# WiiIr.net
KiCad netlist of a schematic drawn in EAGLE
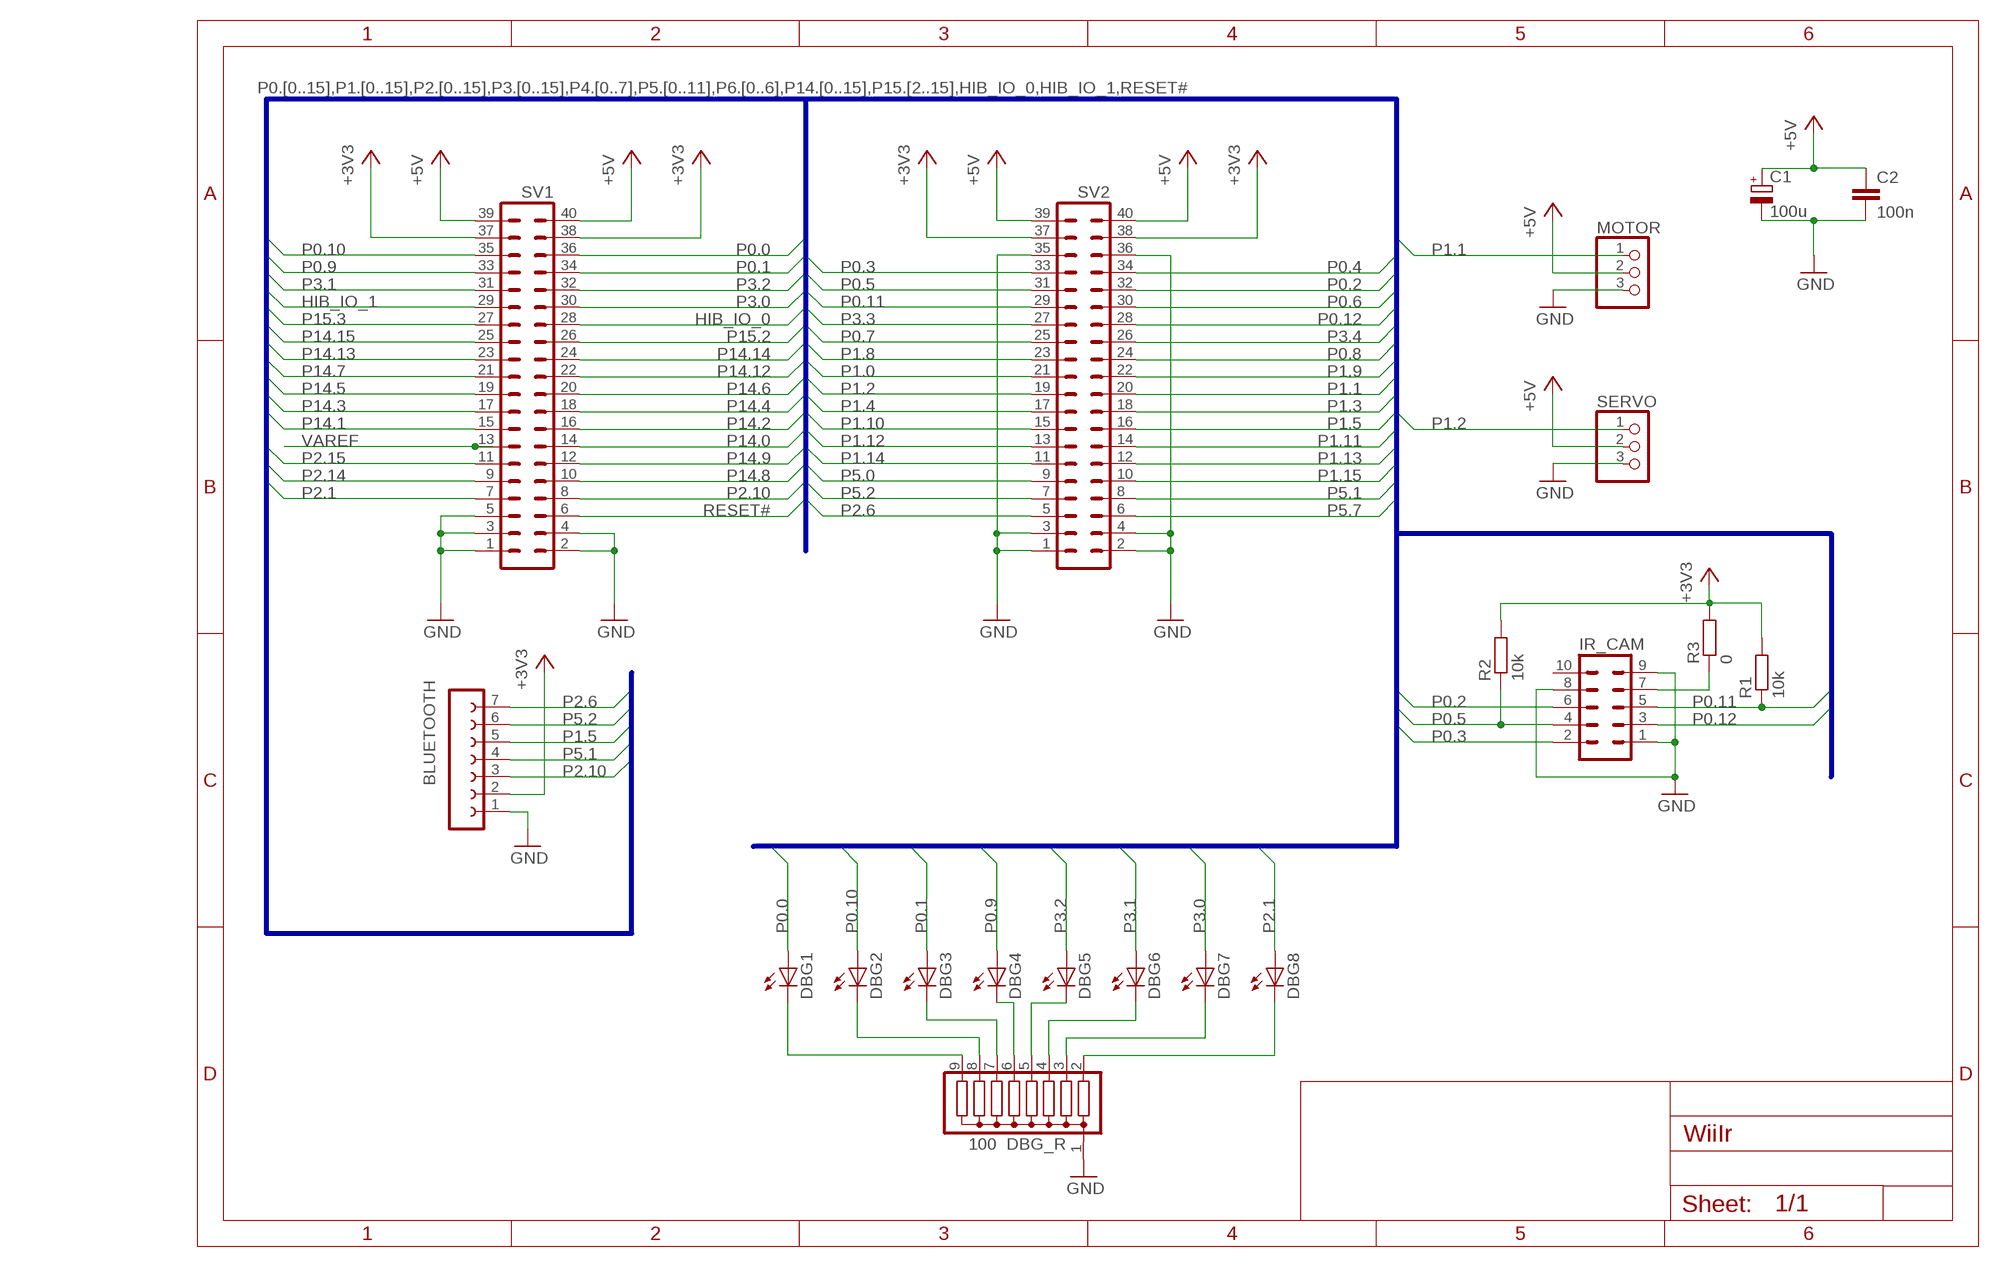
[diagram p0: schematic, sheet 1]

(export (version "E")
  (design (tool "Eeschema 10.0.6"))
  (components
    (comp (ref "BLUETOOTH")
      (value "FE07-1")
      (footprint "eagle-import:FE07")
      (libsource (lib "eagle-import") (part "FE07-1"))
    )
    (comp (ref "C1")
      (value "100u")
      (footprint "eagle-import:E2,5-7")
      (libsource (lib "eagle-import") (part "CPOL-EUE2.5-7"))
    )
    (comp (ref "C2")
      (value "100n")
      (footprint "eagle-import:C050-024X044")
      (libsource (lib "eagle-import") (part "C-EU050-024X044"))
    )
    (comp (ref "DBG1")
      (value "LEDSQR2X5")
      (footprint "eagle-import:LED2X5")
      (libsource (lib "eagle-import") (part "LEDSQR2X5"))
    )
    (comp (ref "DBG2")
      (value "LEDSQR2X5")
      (footprint "eagle-import:LED2X5")
      (libsource (lib "eagle-import") (part "LEDSQR2X5"))
    )
    (comp (ref "DBG3")
      (value "LEDSQR2X5")
      (footprint "eagle-import:LED2X5")
      (libsource (lib "eagle-import") (part "LEDSQR2X5"))
    )
    (comp (ref "DBG4")
      (value "LEDSQR2X5")
      (footprint "eagle-import:LED2X5")
      (libsource (lib "eagle-import") (part "LEDSQR2X5"))
    )
    (comp (ref "DBG5")
      (value "LEDSQR2X5")
      (footprint "eagle-import:LED2X5")
      (libsource (lib "eagle-import") (part "LEDSQR2X5"))
    )
    (comp (ref "DBG6")
      (value "LEDSQR2X5")
      (footprint "eagle-import:LED2X5")
      (libsource (lib "eagle-import") (part "LEDSQR2X5"))
    )
    (comp (ref "DBG7")
      (value "LEDSQR2X5")
      (footprint "eagle-import:LED2X5")
      (libsource (lib "eagle-import") (part "LEDSQR2X5"))
    )
    (comp (ref "DBG8")
      (value "LEDSQR2X5")
      (footprint "eagle-import:LED2X5")
      (libsource (lib "eagle-import") (part "LEDSQR2X5"))
    )
    (comp (ref "DBG_R")
      (value "100")
      (footprint "eagle-import:SIL9")
      (libsource (lib "eagle-import") (part "G08R"))
    )
    (comp (ref "IR_CAM")
      (value "ML10")
      (footprint "eagle-import:ML10")
      (libsource (lib "eagle-import") (part "ML10"))
    )
    (comp (ref "MOTOR")
      (value "PINHD-1X3/90")
      (footprint "eagle-import:1X03_90")
      (libsource (lib "eagle-import") (part "PINHD-1X3/90"))
    )
    (comp (ref "R1")
      (value "10k")
      (footprint "eagle-import:0207_10")
      (libsource (lib "eagle-import") (part "R-EU_0207/10"))
    )
    (comp (ref "R2")
      (value "10k")
      (footprint "eagle-import:0207_10")
      (libsource (lib "eagle-import") (part "R-EU_0207/10"))
    )
    (comp (ref "R3")
      (value "0")
      (footprint "eagle-import:0207_12")
      (libsource (lib "eagle-import") (part "R-EU_0207/12"))
    )
    (comp (ref "SERVO")
      (value "PINHD-1X3/90")
      (footprint "eagle-import:1X03_90")
      (libsource (lib "eagle-import") (part "PINHD-1X3/90"))
    )
    (comp (ref "SV1")
      (value "MA20-2")
      (footprint "eagle-import:MA20-2")
      (libsource (lib "eagle-import") (part "MA20-2"))
    )
    (comp (ref "SV2")
      (value "MA20-2")
      (footprint "eagle-import:MA20-2")
      (libsource (lib "eagle-import") (part "MA20-2"))
    )
  )
  (nets
    (net (code "1") (name "+3V3") (class "Default")
      (node (ref "BLUETOOTH") (pin "2") (pinfunction "2_2") (pintype "passive"))
      (node (ref "R1") (pin "2") (pinfunction "2_2") (pintype "passive"))
      (node (ref "R2") (pin "2") (pinfunction "2_2") (pintype "passive"))
      (node (ref "R3") (pin "2") (pinfunction "2_2") (pintype "passive"))
      (node (ref "SV1") (pin "37") (pinfunction "37_37") (pintype "passive"))
      (node (ref "SV1") (pin "38") (pinfunction "38_38") (pintype "passive"))
      (node (ref "SV2") (pin "37") (pinfunction "37_37") (pintype "passive"))
      (node (ref "SV2") (pin "38") (pinfunction "38_38") (pintype "passive"))
    )
    (net (code "2") (name "+5V") (class "Default")
      (node (ref "C1") (pin "+") (pinfunction "+_+") (pintype "passive"))
      (node (ref "C2") (pin "1") (pinfunction "1_1") (pintype "passive"))
      (node (ref "MOTOR") (pin "2") (pinfunction "2_2") (pintype "passive"))
      (node (ref "SERVO") (pin "2") (pinfunction "2_2") (pintype "passive"))
      (node (ref "SV1") (pin "39") (pinfunction "39_39") (pintype "passive"))
      (node (ref "SV1") (pin "40") (pinfunction "40_40") (pintype "passive"))
      (node (ref "SV2") (pin "39") (pinfunction "39_39") (pintype "passive"))
      (node (ref "SV2") (pin "40") (pinfunction "40_40") (pintype "passive"))
    )
    (net (code "3") (name "/HIB_IO_0") (class "Default")
      (node (ref "SV1") (pin "28") (pinfunction "28_28") (pintype "passive"))
    )
    (net (code "4") (name "/HIB_IO_1") (class "Default")
      (node (ref "SV1") (pin "29") (pinfunction "29_29") (pintype "passive"))
    )
    (net (code "5") (name "/P0.0") (class "Default")
      (node (ref "DBG1") (pin "A") (pinfunction "A_A") (pintype "passive"))
      (node (ref "SV1") (pin "36") (pinfunction "36_36") (pintype "passive"))
    )
    (net (code "6") (name "/P0.1") (class "Default")
      (node (ref "DBG3") (pin "A") (pinfunction "A_A") (pintype "passive"))
      (node (ref "SV1") (pin "34") (pinfunction "34_34") (pintype "passive"))
    )
    (net (code "7") (name "/P0.2") (class "Default")
      (node (ref "IR_CAM") (pin "6") (pinfunction "6_6") (pintype "passive"))
      (node (ref "SV2") (pin "32") (pinfunction "32_32") (pintype "passive"))
    )
    (net (code "8") (name "/P0.3") (class "Default")
      (node (ref "IR_CAM") (pin "2") (pinfunction "2_2") (pintype "passive"))
      (node (ref "SV2") (pin "33") (pinfunction "33_33") (pintype "passive"))
    )
    (net (code "9") (name "/P0.4") (class "Default")
      (node (ref "SV2") (pin "34") (pinfunction "34_34") (pintype "passive"))
    )
    (net (code "10") (name "/P0.5") (class "Default")
      (node (ref "IR_CAM") (pin "4") (pinfunction "4_4") (pintype "passive"))
      (node (ref "R2") (pin "1") (pinfunction "1_1") (pintype "passive"))
      (node (ref "SV2") (pin "31") (pinfunction "31_31") (pintype "passive"))
    )
    (net (code "11") (name "/P0.6") (class "Default")
      (node (ref "SV2") (pin "30") (pinfunction "30_30") (pintype "passive"))
    )
    (net (code "12") (name "/P0.7") (class "Default")
      (node (ref "SV2") (pin "25") (pinfunction "25_25") (pintype "passive"))
    )
    (net (code "13") (name "/P0.8") (class "Default")
      (node (ref "SV2") (pin "24") (pinfunction "24_24") (pintype "passive"))
    )
    (net (code "14") (name "/P0.9") (class "Default")
      (node (ref "DBG4") (pin "A") (pinfunction "A_A") (pintype "passive"))
      (node (ref "SV1") (pin "33") (pinfunction "33_33") (pintype "passive"))
    )
    (net (code "15") (name "/P0.10") (class "Default")
      (node (ref "DBG2") (pin "A") (pinfunction "A_A") (pintype "passive"))
      (node (ref "SV1") (pin "35") (pinfunction "35_35") (pintype "passive"))
    )
    (net (code "16") (name "/P0.11") (class "Default")
      (node (ref "IR_CAM") (pin "5") (pinfunction "5_5") (pintype "passive"))
      (node (ref "R1") (pin "1") (pinfunction "1_1") (pintype "passive"))
      (node (ref "SV2") (pin "29") (pinfunction "29_29") (pintype "passive"))
    )
    (net (code "17") (name "/P0.12") (class "Default")
      (node (ref "IR_CAM") (pin "3") (pinfunction "3_3") (pintype "passive"))
      (node (ref "SV2") (pin "28") (pinfunction "28_28") (pintype "passive"))
    )
    (net (code "18") (name "/P1.0") (class "Default")
      (node (ref "SV2") (pin "21") (pinfunction "21_21") (pintype "passive"))
    )
    (net (code "19") (name "/P1.1") (class "Default")
      (node (ref "MOTOR") (pin "1") (pinfunction "1_1") (pintype "passive"))
      (node (ref "SV2") (pin "20") (pinfunction "20_20") (pintype "passive"))
    )
    (net (code "20") (name "/P1.2") (class "Default")
      (node (ref "SERVO") (pin "1") (pinfunction "1_1") (pintype "passive"))
      (node (ref "SV2") (pin "19") (pinfunction "19_19") (pintype "passive"))
    )
    (net (code "21") (name "/P1.3") (class "Default")
      (node (ref "SV2") (pin "18") (pinfunction "18_18") (pintype "passive"))
    )
    (net (code "22") (name "/P1.4") (class "Default")
      (node (ref "SV2") (pin "17") (pinfunction "17_17") (pintype "passive"))
    )
    (net (code "23") (name "/P1.5") (class "Default")
      (node (ref "BLUETOOTH") (pin "5") (pinfunction "5_5") (pintype "passive"))
      (node (ref "SV2") (pin "16") (pinfunction "16_16") (pintype "passive"))
    )
    (net (code "24") (name "/P1.8") (class "Default")
      (node (ref "SV2") (pin "23") (pinfunction "23_23") (pintype "passive"))
    )
    (net (code "25") (name "/P1.9") (class "Default")
      (node (ref "SV2") (pin "22") (pinfunction "22_22") (pintype "passive"))
    )
    (net (code "26") (name "/P1.10") (class "Default")
      (node (ref "SV2") (pin "15") (pinfunction "15_15") (pintype "passive"))
    )
    (net (code "27") (name "/P1.11") (class "Default")
      (node (ref "SV2") (pin "14") (pinfunction "14_14") (pintype "passive"))
    )
    (net (code "28") (name "/P1.12") (class "Default")
      (node (ref "SV2") (pin "13") (pinfunction "13_13") (pintype "passive"))
    )
    (net (code "29") (name "/P1.13") (class "Default")
      (node (ref "SV2") (pin "12") (pinfunction "12_12") (pintype "passive"))
    )
    (net (code "30") (name "/P1.14") (class "Default")
      (node (ref "SV2") (pin "11") (pinfunction "11_11") (pintype "passive"))
    )
    (net (code "31") (name "/P1.15") (class "Default")
      (node (ref "SV2") (pin "10") (pinfunction "10_10") (pintype "passive"))
    )
    (net (code "32") (name "/P2.1") (class "Default")
      (node (ref "DBG8") (pin "A") (pinfunction "A_A") (pintype "passive"))
      (node (ref "SV1") (pin "7") (pinfunction "7_7") (pintype "passive"))
    )
    (net (code "33") (name "/P2.6") (class "Default")
      (node (ref "BLUETOOTH") (pin "7") (pinfunction "7_7") (pintype "passive"))
      (node (ref "SV2") (pin "5") (pinfunction "5_5") (pintype "passive"))
    )
    (net (code "34") (name "/P2.10") (class "Default")
      (node (ref "BLUETOOTH") (pin "3") (pinfunction "3_3") (pintype "passive"))
      (node (ref "SV1") (pin "8") (pinfunction "8_8") (pintype "passive"))
    )
    (net (code "35") (name "/P2.14") (class "Default")
      (node (ref "SV1") (pin "9") (pinfunction "9_9") (pintype "passive"))
    )
    (net (code "36") (name "/P2.15") (class "Default")
      (node (ref "SV1") (pin "11") (pinfunction "11_11") (pintype "passive"))
    )
    (net (code "37") (name "/P3.0") (class "Default")
      (node (ref "DBG7") (pin "A") (pinfunction "A_A") (pintype "passive"))
      (node (ref "SV1") (pin "30") (pinfunction "30_30") (pintype "passive"))
    )
    (net (code "38") (name "/P3.1") (class "Default")
      (node (ref "DBG6") (pin "A") (pinfunction "A_A") (pintype "passive"))
      (node (ref "SV1") (pin "31") (pinfunction "31_31") (pintype "passive"))
    )
    (net (code "39") (name "/P3.2") (class "Default")
      (node (ref "DBG5") (pin "A") (pinfunction "A_A") (pintype "passive"))
      (node (ref "SV1") (pin "32") (pinfunction "32_32") (pintype "passive"))
    )
    (net (code "40") (name "/P3.3") (class "Default")
      (node (ref "SV2") (pin "27") (pinfunction "27_27") (pintype "passive"))
    )
    (net (code "41") (name "/P3.4") (class "Default")
      (node (ref "SV2") (pin "26") (pinfunction "26_26") (pintype "passive"))
    )
    (net (code "42") (name "/P5.0") (class "Default")
      (node (ref "SV2") (pin "9") (pinfunction "9_9") (pintype "passive"))
    )
    (net (code "43") (name "/P5.1") (class "Default")
      (node (ref "BLUETOOTH") (pin "4") (pinfunction "4_4") (pintype "passive"))
      (node (ref "SV2") (pin "8") (pinfunction "8_8") (pintype "passive"))
    )
    (net (code "44") (name "/P5.2") (class "Default")
      (node (ref "BLUETOOTH") (pin "6") (pinfunction "6_6") (pintype "passive"))
      (node (ref "SV2") (pin "7") (pinfunction "7_7") (pintype "passive"))
    )
    (net (code "45") (name "/P5.7") (class "Default")
      (node (ref "SV2") (pin "6") (pinfunction "6_6") (pintype "passive"))
    )
    (net (code "46") (name "/P14.0") (class "Default")
      (node (ref "SV1") (pin "14") (pinfunction "14_14") (pintype "passive"))
    )
    (net (code "47") (name "/P14.1") (class "Default")
      (node (ref "SV1") (pin "15") (pinfunction "15_15") (pintype "passive"))
    )
    (net (code "48") (name "/P14.2") (class "Default")
      (node (ref "SV1") (pin "16") (pinfunction "16_16") (pintype "passive"))
    )
    (net (code "49") (name "/P14.3") (class "Default")
      (node (ref "SV1") (pin "17") (pinfunction "17_17") (pintype "passive"))
    )
    (net (code "50") (name "/P14.4") (class "Default")
      (node (ref "SV1") (pin "18") (pinfunction "18_18") (pintype "passive"))
    )
    (net (code "51") (name "/P14.5") (class "Default")
      (node (ref "SV1") (pin "19") (pinfunction "19_19") (pintype "passive"))
    )
    (net (code "52") (name "/P14.6") (class "Default")
      (node (ref "SV1") (pin "20") (pinfunction "20_20") (pintype "passive"))
    )
    (net (code "53") (name "/P14.7") (class "Default")
      (node (ref "SV1") (pin "21") (pinfunction "21_21") (pintype "passive"))
    )
    (net (code "54") (name "/P14.8") (class "Default")
      (node (ref "SV1") (pin "10") (pinfunction "10_10") (pintype "passive"))
    )
    (net (code "55") (name "/P14.9") (class "Default")
      (node (ref "SV1") (pin "12") (pinfunction "12_12") (pintype "passive"))
    )
    (net (code "56") (name "/P14.12") (class "Default")
      (node (ref "SV1") (pin "22") (pinfunction "22_22") (pintype "passive"))
    )
    (net (code "57") (name "/P14.13") (class "Default")
      (node (ref "SV1") (pin "23") (pinfunction "23_23") (pintype "passive"))
    )
    (net (code "58") (name "/P14.14") (class "Default")
      (node (ref "SV1") (pin "24") (pinfunction "24_24") (pintype "passive"))
    )
    (net (code "59") (name "/P14.15") (class "Default")
      (node (ref "SV1") (pin "25") (pinfunction "25_25") (pintype "passive"))
    )
    (net (code "60") (name "/P15.2") (class "Default")
      (node (ref "SV1") (pin "26") (pinfunction "26_26") (pintype "passive"))
    )
    (net (code "61") (name "/P15.3") (class "Default")
      (node (ref "SV1") (pin "27") (pinfunction "27_27") (pintype "passive"))
    )
    (net (code "62") (name "/RESET#") (class "Default")
      (node (ref "SV1") (pin "6") (pinfunction "6_6") (pintype "passive"))
    )
    (net (code "63") (name "/VAREF") (class "Default")
      (node (ref "SV1") (pin "13") (pinfunction "13_13") (pintype "passive"))
    )
    (net (code "65") (name "GND") (class "Default")
      (node (ref "BLUETOOTH") (pin "1") (pinfunction "1_1") (pintype "passive"))
      (node (ref "C1") (pin "-") (pinfunction "-_-") (pintype "passive"))
      (node (ref "C2") (pin "2") (pinfunction "2_2") (pintype "passive"))
      (node (ref "DBG_R") (pin "1") (pinfunction "1_1") (pintype "passive"))
      (node (ref "IR_CAM") (pin "1") (pinfunction "1_1") (pintype "passive"))
      (node (ref "IR_CAM") (pin "8") (pinfunction "8_8") (pintype "passive"))
      (node (ref "IR_CAM") (pin "9") (pinfunction "9_9") (pintype "passive"))
      (node (ref "MOTOR") (pin "3") (pinfunction "3_3") (pintype "passive"))
      (node (ref "SERVO") (pin "3") (pinfunction "3_3") (pintype "passive"))
      (node (ref "SV1") (pin "1") (pinfunction "1_1") (pintype "passive"))
      (node (ref "SV1") (pin "2") (pinfunction "2_2") (pintype "passive"))
      (node (ref "SV1") (pin "3") (pinfunction "3_3") (pintype "passive"))
      (node (ref "SV1") (pin "4") (pinfunction "4_4") (pintype "passive"))
      (node (ref "SV1") (pin "5") (pinfunction "5_5") (pintype "passive"))
      (node (ref "SV2") (pin "1") (pinfunction "1_1") (pintype "passive"))
      (node (ref "SV2") (pin "2") (pinfunction "2_2") (pintype "passive"))
      (node (ref "SV2") (pin "3") (pinfunction "3_3") (pintype "passive"))
      (node (ref "SV2") (pin "35") (pinfunction "35_35") (pintype "passive"))
      (node (ref "SV2") (pin "36") (pinfunction "36_36") (pintype "passive"))
      (node (ref "SV2") (pin "4") (pinfunction "4_4") (pintype "passive"))
    )
    (net (code "66") (name "Net-(DBG1-C)") (class "Default")
      (node (ref "DBG1") (pin "K") (pinfunction "C_K") (pintype "passive"))
      (node (ref "DBG_R") (pin "9") (pinfunction "9_9") (pintype "passive"))
    )
    (net (code "67") (name "Net-(DBG2-C)") (class "Default")
      (node (ref "DBG2") (pin "K") (pinfunction "C_K") (pintype "passive"))
      (node (ref "DBG_R") (pin "8") (pinfunction "8_8") (pintype "passive"))
    )
    (net (code "68") (name "Net-(DBG3-C)") (class "Default")
      (node (ref "DBG3") (pin "K") (pinfunction "C_K") (pintype "passive"))
      (node (ref "DBG_R") (pin "7") (pinfunction "7_7") (pintype "passive"))
    )
    (net (code "69") (name "Net-(DBG4-C)") (class "Default")
      (node (ref "DBG4") (pin "K") (pinfunction "C_K") (pintype "passive"))
      (node (ref "DBG_R") (pin "6") (pinfunction "6_6") (pintype "passive"))
    )
    (net (code "70") (name "Net-(DBG5-C)") (class "Default")
      (node (ref "DBG5") (pin "K") (pinfunction "C_K") (pintype "passive"))
      (node (ref "DBG_R") (pin "5") (pinfunction "5_5") (pintype "passive"))
    )
    (net (code "71") (name "Net-(DBG6-C)") (class "Default")
      (node (ref "DBG6") (pin "K") (pinfunction "C_K") (pintype "passive"))
      (node (ref "DBG_R") (pin "4") (pinfunction "4_4") (pintype "passive"))
    )
    (net (code "72") (name "Net-(DBG7-C)") (class "Default")
      (node (ref "DBG7") (pin "K") (pinfunction "C_K") (pintype "passive"))
      (node (ref "DBG_R") (pin "3") (pinfunction "3_3") (pintype "passive"))
    )
    (net (code "73") (name "Net-(DBG8-C)") (class "Default")
      (node (ref "DBG8") (pin "K") (pinfunction "C_K") (pintype "passive"))
      (node (ref "DBG_R") (pin "2") (pinfunction "2_2") (pintype "passive"))
    )
    (net (code "74") (name "Net-(IR_CAM-Pad7)") (class "Default")
      (node (ref "IR_CAM") (pin "7") (pinfunction "7_7") (pintype "passive"))
      (node (ref "R3") (pin "1") (pinfunction "1_1") (pintype "passive"))
    )
    (net (code "75") (name "unconnected-(IR_CAM-Pad10)") (class "Default")
      (node (ref "IR_CAM") (pin "10") (pinfunction "10_10") (pintype "passive"))
    )
  )
)
